# Current_Driver_v1.net
KiCad netlist of a schematic drawn in EAGLE
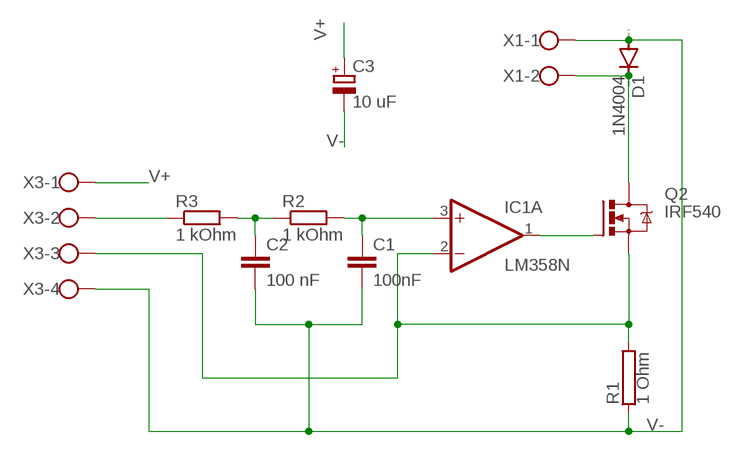
[diagram p0: schematic, sheet 1]

(export (version "E")
  (design (tool "Eeschema 10.0.6"))
  (components
    (comp (ref "C1")
      (value "100nF")
      (footprint "eagle-import:C050-030X075")
      (libsource (lib "eagle-import") (part "C-EU050-030X075"))
    )
    (comp (ref "C2")
      (value "100 nF")
      (footprint "eagle-import:C050-030X075")
      (libsource (lib "eagle-import") (part "C-EU050-030X075"))
    )
    (comp (ref "C3")
      (value "10 uF")
      (footprint "eagle-import:E2,5-6E")
      (libsource (lib "eagle-import") (part "CPOL-EUE2,5-6E"))
    )
    (comp (ref "D1")
      (value "1N4004")
      (footprint "eagle-import:DO41-10")
      (libsource (lib "eagle-import") (part "1N4004"))
    )
    (comp (ref "IC1")
      (value "LM358N")
      (footprint "eagle-import:DIL08")
      (libsource (lib "eagle-import") (part "LM358N"))
    )
    (comp (ref "Q2")
      (value "IRF540")
      (footprint "eagle-import:TO220BV")
      (libsource (lib "eagle-import") (part "IRF540"))
    )
    (comp (ref "R1")
      (value "1 Ohm")
      (footprint "eagle-import:AC05")
      (libsource (lib "eagle-import") (part "RAC05"))
    )
    (comp (ref "R2")
      (value "1 kOhm")
      (footprint "eagle-import:0204_7")
      (libsource (lib "eagle-import") (part "R-EU_0204/7"))
    )
    (comp (ref "R3")
      (value "1 kOhm")
      (footprint "eagle-import:0204_7")
      (libsource (lib "eagle-import") (part "R-EU_0204/7"))
    )
    (comp (ref "X1")
      (value "W237-102")
      (footprint "eagle-import:W237-102")
      (fields (field (name "MPN") "237-102"))
      (libsource (lib "eagle-import") (part "W237-102"))
    )
    (comp (ref "X3")
      (value "W237-4")
      (footprint "eagle-import:W237-4")
      (libsource (lib "eagle-import") (part "W237-4"))
    )
  )
  (nets
    (net (code "1") (name "/V+") (class "Default")
      (node (ref "C3") (pin "+") (pinfunction "+_+") (pintype "passive"))
      (node (ref "X3") (pin "1") (pinfunction "KL_1") (pintype "passive"))
    )
    (net (code "2") (name "/V-") (class "Default")
      (node (ref "C1") (pin "2") (pinfunction "2_2") (pintype "passive"))
      (node (ref "C2") (pin "2") (pinfunction "2_2") (pintype "passive"))
      (node (ref "C3") (pin "-") (pinfunction "-_-") (pintype "passive"))
      (node (ref "D1") (pin "A") (pinfunction "A_A") (pintype "passive"))
      (node (ref "R1") (pin "1") (pinfunction "1_1") (pintype "passive"))
      (node (ref "X1") (pin "1") (pinfunction "KL_1") (pintype "passive"))
      (node (ref "X3") (pin "4") (pinfunction "KL_4") (pintype "passive"))
    )
    (net (code "3") (name "Net-(C2-Pad1)") (class "Default")
      (node (ref "C2") (pin "1") (pinfunction "1_1") (pintype "passive"))
      (node (ref "R2") (pin "1") (pinfunction "1_1") (pintype "passive"))
      (node (ref "R3") (pin "2") (pinfunction "2_2") (pintype "passive"))
    )
    (net (code "4") (name "Net-(IC1A-+IN)") (class "Default")
      (node (ref "C1") (pin "1") (pinfunction "1_1") (pintype "passive"))
      (node (ref "IC1") (pin "3") (pinfunction "+IN_3") (pintype "input"))
      (node (ref "R2") (pin "2") (pinfunction "2_2") (pintype "passive"))
    )
    (net (code "5") (name "Net-(IC1A--IN)") (class "Default")
      (node (ref "IC1") (pin "2") (pinfunction "-IN_2") (pintype "input"))
      (node (ref "Q2") (pin "S") (pinfunction "S_S") (pintype "passive"))
      (node (ref "R1") (pin "2") (pinfunction "2_2") (pintype "passive"))
      (node (ref "X3") (pin "3") (pinfunction "KL_3") (pintype "passive"))
    )
    (net (code "6") (name "Net-(IC1A-OUT)") (class "Default")
      (node (ref "IC1") (pin "1") (pinfunction "OUT_1") (pintype "output"))
      (node (ref "Q2") (pin "G") (pinfunction "G_G") (pintype "passive"))
    )
    (net (code "7") (name "Net-(X1B-KL)") (class "Default")
      (node (ref "D1") (pin "C") (pinfunction "C_C") (pintype "passive"))
      (node (ref "Q2") (pin "D") (pinfunction "D_D") (pintype "passive"))
      (node (ref "X1") (pin "2") (pinfunction "KL_2") (pintype "passive"))
    )
    (net (code "8") (name "Net-(X3B-KL)") (class "Default")
      (node (ref "R3") (pin "1") (pinfunction "1_1") (pintype "passive"))
      (node (ref "X3") (pin "2") (pinfunction "KL_2") (pintype "passive"))
    )
  )
)
